# Ref_1V8_LM4132AMF.net
KiCad netlist of a schematic drawn in Altium Designer
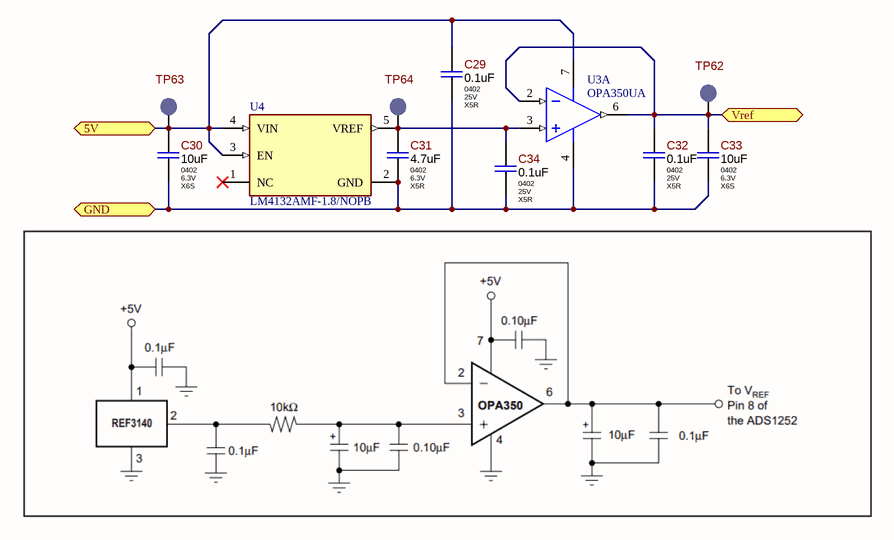
[diagram p0: Ref_1V8_LM4132AMF.SchDoc]

(export (version "E")
  (design (tool "Eeschema 10.0.6"))
  (components
    (comp (ref "C29")
      (value "0.1uF")
      (footprint "C_CERAMIC_0402_MED")
      (description "100nF 25V X5R ±10% 0402 Ceramic Capacitor RoHS")
      (fields
        (field (name "PACKAGE") "0402")
        (field (name "VOLTAGE") "25V")
        (field (name "DIELECTRIC TYPE") "X5R")
        (field (name "PART NUMBER") "CL05A104KA5NNNC")
        (field (name "MANUFACTURER") "Samsung Electro-Mechanics")
      )
      (libsource (lib "EL.XXX.T01") (part "Capacitor-NonPolar"))
    )
    (comp (ref "C30")
      (value "10uF")
      (footprint "C_CERAMIC_0402_MED")
      (description "10uF 6.3V X6S ±20% 0402 Ceramic Capacitor RoHS")
      (fields
        (field (name "PACKAGE") "0402")
        (field (name "VOLTAGE") "6.3V")
        (field (name "DIELECTRIC TYPE") "X6S")
        (field (name "PART NUMBER") "GRM155C80J106ME11D")
        (field (name "MANUFACTURER") "Murata Electronics")
      )
      (libsource (lib "EL.XXX.T01") (part "Capacitor-NonPolar"))
    )
    (comp (ref "C31")
      (value "4.7uF")
      (footprint "C_CERAMIC_0402_MED")
      (description "4.7uF 6.3V X5R ±20% 0402 Ceramic Capacitor RoHS")
      (fields
        (field (name "PACKAGE") "0402")
        (field (name "VOLTAGE") "6.3V")
        (field (name "DIELECTRIC TYPE") "X5R")
        (field (name "PART NUMBER") "GRM155R60J475ME47")
        (field (name "MANUFACTURER") "Murata Electronics")
      )
      (libsource (lib "EL.XXX.T01") (part "Capacitor-NonPolar"))
    )
    (comp (ref "C32")
      (value "0.1uF")
      (footprint "C_CERAMIC_0402_MED")
      (description "100nF 25V X5R ±10% 0402 Ceramic Capacitor RoHS")
      (fields
        (field (name "PACKAGE") "0402")
        (field (name "VOLTAGE") "25V")
        (field (name "DIELECTRIC TYPE") "X5R")
        (field (name "PART NUMBER") "CL05A104KA5NNNC")
        (field (name "MANUFACTURER") "Samsung Electro-Mechanics")
      )
      (libsource (lib "EL.XXX.T01") (part "Capacitor-NonPolar"))
    )
    (comp (ref "C33")
      (value "10uF")
      (footprint "C_CERAMIC_0402_MED")
      (description "10uF 6.3V X6S ±20% 0402 Ceramic Capacitor RoHS")
      (fields
        (field (name "PACKAGE") "0402")
        (field (name "VOLTAGE") "6.3V")
        (field (name "DIELECTRIC TYPE") "X6S")
        (field (name "PART NUMBER") "GRM155C80J106ME11D")
        (field (name "MANUFACTURER") "Murata Electronics")
      )
      (libsource (lib "EL.XXX.T01") (part "Capacitor-NonPolar"))
    )
    (comp (ref "C34")
      (value "0.1uF")
      (footprint "C_CERAMIC_0402_MED")
      (description "100nF 25V X5R ±10% 0402 Ceramic Capacitor RoHS")
      (fields
        (field (name "PACKAGE") "0402")
        (field (name "VOLTAGE") "25V")
        (field (name "DIELECTRIC TYPE") "X5R")
        (field (name "PART NUMBER") "CL05A104KA5NNNC")
        (field (name "MANUFACTURER") "Samsung Electro-Mechanics")
      )
      (libsource (lib "EL.XXX.T01") (part "Capacitor-NonPolar"))
    )
    (comp (ref "TP62")
      (value "LED_LINK")
      (footprint "TP_SMD_2mm")
      (description "Test Point SMD Pad 1.0mm/1.5mm/2mm")
      (fields (field (name "PART NUMBER") "TP-PAD-SMD"))
      (libsource (lib "EL.XXX.T01") (part "Test-Point-SMD-1"))
    )
    (comp (ref "TP63")
      (value "LED_LINK")
      (footprint "TP_SMD_2mm")
      (description "Test Point SMD Pad 1.0mm/1.5mm/2mm")
      (fields (field (name "PART NUMBER") "TP-PAD-SMD"))
      (libsource (lib "EL.XXX.T01") (part "Test-Point-SMD-1"))
    )
    (comp (ref "TP64")
      (value "LED_LINK")
      (footprint "TP_SMD_2mm")
      (description "Test Point SMD Pad 1.0mm/1.5mm/2mm")
      (fields (field (name "PART NUMBER") "TP-PAD-SMD"))
      (libsource (lib "EL.XXX.T01") (part "Test-Point-SMD-1"))
    )
    (comp (ref "U3")
      (value "OPA350UA")
      (footprint "D0008A_M")
      (fields (field (name "MANUFACTURER") "Texas Instruments"))
      (libsource (lib "EL.XXX.T01") (part "TI-OPA-8_1"))
    )
    (comp (ref "U4")
      (value "LM4132AMF-1.8/NOPB")
      (footprint "SOT-23-5")
      (description "IC VREF SERIES 0.05% SOT23-5")
      (fields (field (name "TOLERANCE") "0.05%"))
      (libsource (lib "EL.XXX.T01") (part "LM4132AMF-1.8/NOPB"))
    )
  )
  (nets
    (net (code "1") (name "/5V") (class "Default")
      (node (ref "C29") (pin "1") (pinfunction "1_1") (pintype "passive"))
      (node (ref "C30") (pin "1") (pinfunction "1_1") (pintype "passive"))
      (node (ref "TP63") (pin "1") (pintype "passive"))
      (node (ref "U3") (pin "7") (pinfunction "V+_7") (pintype "power_in"))
      (node (ref "U4") (pin "3") (pinfunction "EN_3") (pintype "input"))
      (node (ref "U4") (pin "4") (pinfunction "VIN_4") (pintype "input"))
    )
    (net (code "2") (name "/GND") (class "Default")
      (node (ref "C29") (pin "2") (pinfunction "2_2") (pintype "passive"))
      (node (ref "C30") (pin "2") (pinfunction "2_2") (pintype "passive"))
      (node (ref "C31") (pin "2") (pinfunction "2_2") (pintype "passive"))
      (node (ref "C32") (pin "2") (pinfunction "2_2") (pintype "passive"))
      (node (ref "C33") (pin "2") (pinfunction "2_2") (pintype "passive"))
      (node (ref "C34") (pin "2") (pinfunction "2_2") (pintype "passive"))
      (node (ref "U3") (pin "4") (pinfunction "V-_4") (pintype "power_in"))
      (node (ref "U4") (pin "2") (pinfunction "GND_2") (pintype "power_in"))
    )
    (net (code "3") (name "/Vref") (class "Default")
      (node (ref "C32") (pin "1") (pinfunction "1_1") (pintype "passive"))
      (node (ref "C33") (pin "1") (pinfunction "1_1") (pintype "passive"))
      (node (ref "TP62") (pin "1") (pintype "passive"))
      (node (ref "U3") (pin "2") (pinfunction "IN-_2") (pintype "input"))
      (node (ref "U3") (pin "6") (pinfunction "OUT_6") (pintype "output"))
    )
    (net (code "4") (name "Net-(U3A-IN+)") (class "Default")
      (node (ref "C31") (pin "1") (pinfunction "1_1") (pintype "passive"))
      (node (ref "C34") (pin "1") (pinfunction "1_1") (pintype "passive"))
      (node (ref "TP64") (pin "1") (pintype "passive"))
      (node (ref "U3") (pin "3") (pinfunction "IN+_3") (pintype "input"))
      (node (ref "U4") (pin "5") (pinfunction "VREF_5") (pintype "output"))
    )
    (net (code "5") (name "unconnected-(U4-NC-Pad1)") (class "Default")
      (node (ref "U4") (pin "1") (pinfunction "NC_1") (pintype "passive+no_connect"))
    )
  )
)
